# lcd_reverse_engineering_rig.net
KiCad netlist of a schematic drawn in Altium Designer
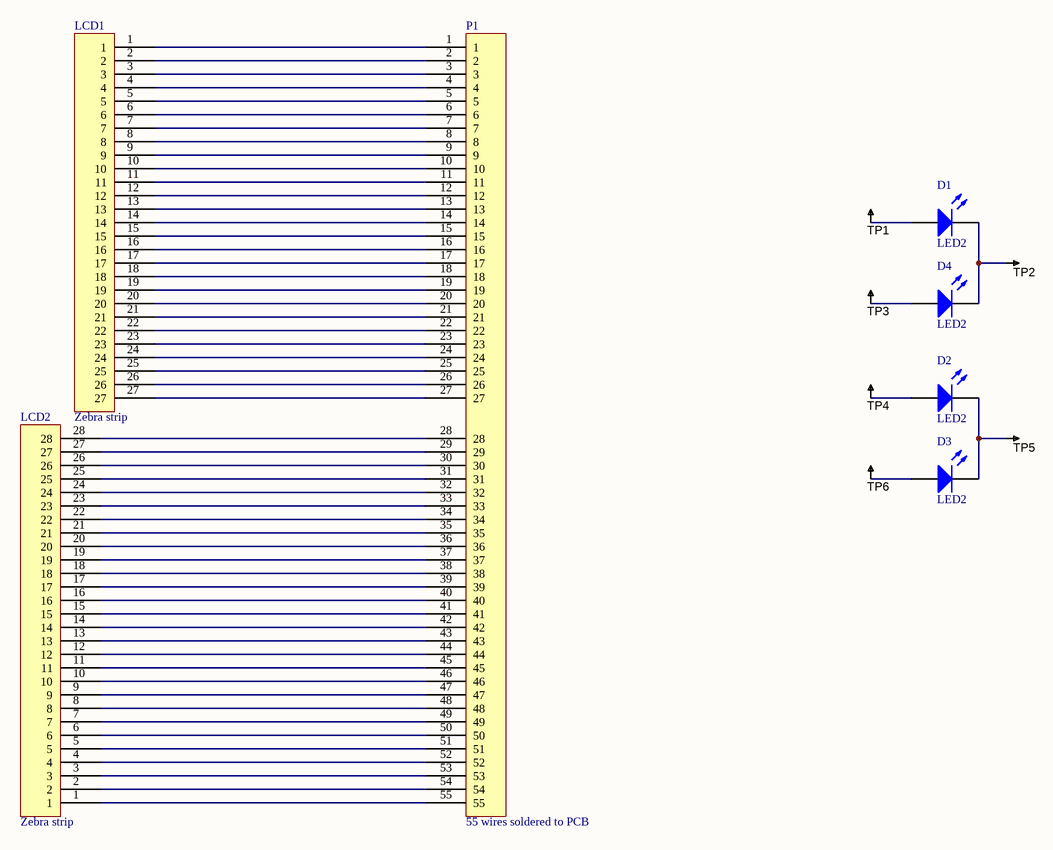
[diagram p0: lcd_reverse_engineering_rig.SchDoc]

(export (version "E")
  (design (tool "Eeschema 10.0.6"))
  (components
    (comp (ref "D1")
      (value "LED2")
      (footprint "LED_0802_90deg")
      (description "Typical RED, GREEN, YELLOW, AMBER GaAs LED")
      (fields (field (name "PUBLISHER") "Altium Limited"))
      (libsource (lib "Miscellaneous Devices") (part "LED2"))
    )
    (comp (ref "D2")
      (value "LED2")
      (footprint "LED_0802_90deg")
      (description "Typical RED, GREEN, YELLOW, AMBER GaAs LED")
      (fields (field (name "PUBLISHER") "Altium Limited"))
      (libsource (lib "Miscellaneous Devices") (part "LED2"))
    )
    (comp (ref "D3")
      (value "LED2")
      (footprint "LED_0802_90deg")
      (description "Typical RED, GREEN, YELLOW, AMBER GaAs LED")
      (fields (field (name "PUBLISHER") "Altium Limited"))
      (libsource (lib "Miscellaneous Devices") (part "LED2"))
    )
    (comp (ref "D4")
      (value "LED2")
      (footprint "LED_0802_90deg")
      (description "Typical RED, GREEN, YELLOW, AMBER GaAs LED")
      (fields (field (name "PUBLISHER") "Altium Limited"))
      (libsource (lib "Miscellaneous Devices") (part "LED2"))
    )
    (comp (ref "LCD1")
      (value "Zebra strip")
      (footprint "LCD_Connector_27")
      (description "Zebra strip connector to LCD module (27 pins)")
      (libsource (lib "watch") (part "Zebra strip 27 pin"))
    )
    (comp (ref "LCD2")
      (value "Zebra strip")
      (footprint "LCD_Connector_28")
      (description "Zebra strip connector to LCD module (28 pins)")
      (libsource (lib "watch") (part "Zebra strip 28 pin"))
    )
    (comp (ref "P1")
      (value "55 wires soldered to PCB")
      (footprint "Wires55")
      (libsource (lib "watch") (part "Wires55"))
    )
    (comp (ref "TP1")
      (value "TESTPOINT_THT_MINI")
      (footprint "THP_D38_T75_B75")
      (description "Test Point PCB mount Miniature White")
      (fields (field (name "PBL PART NUMBER") "3100-567"))
      (libsource (lib "PBL - Test Points") (part "TESTPOINT_THT_MINI"))
    )
    (comp (ref "TP2")
      (value "TESTPOINT_THT_MINI")
      (footprint "THP_D38_T75_B75")
      (description "Test Point PCB mount Miniature White")
      (fields (field (name "PBL PART NUMBER") "3100-567"))
      (libsource (lib "PBL - Test Points") (part "TESTPOINT_THT_MINI"))
    )
    (comp (ref "TP3")
      (value "TESTPOINT_THT_MINI")
      (footprint "THP_D38_T75_B75")
      (description "Test Point PCB mount Miniature White")
      (fields (field (name "PBL PART NUMBER") "3100-567"))
      (libsource (lib "PBL - Test Points") (part "TESTPOINT_THT_MINI"))
    )
    (comp (ref "TP4")
      (value "TESTPOINT_THT_MINI")
      (footprint "THP_D38_T75_B75")
      (description "Test Point PCB mount Miniature White")
      (fields (field (name "PBL PART NUMBER") "3100-567"))
      (libsource (lib "PBL - Test Points") (part "TESTPOINT_THT_MINI"))
    )
    (comp (ref "TP5")
      (value "TESTPOINT_THT_MINI")
      (footprint "THP_D38_T75_B75")
      (description "Test Point PCB mount Miniature White")
      (fields (field (name "PBL PART NUMBER") "3100-567"))
      (libsource (lib "PBL - Test Points") (part "TESTPOINT_THT_MINI"))
    )
    (comp (ref "TP6")
      (value "TESTPOINT_THT_MINI")
      (footprint "THP_D38_T75_B75")
      (description "Test Point PCB mount Miniature White")
      (fields (field (name "PBL PART NUMBER") "3100-567"))
      (libsource (lib "PBL - Test Points") (part "TESTPOINT_THT_MINI"))
    )
  )
  (nets
    (net (code "1") (name "Net-(D1-A)") (class "Default")
      (node (ref "D1") (pin "1") (pinfunction "A_1") (pintype "passive"))
      (node (ref "TP1") (pin "1") (pintype "passive"))
    )
    (net (code "2") (name "Net-(D1-K)") (class "Default")
      (node (ref "D1") (pin "2") (pinfunction "K_2") (pintype "passive"))
      (node (ref "D4") (pin "2") (pinfunction "K_2") (pintype "passive"))
      (node (ref "TP2") (pin "1") (pintype "passive"))
    )
    (net (code "3") (name "Net-(D2-A)") (class "Default")
      (node (ref "D2") (pin "1") (pinfunction "A_1") (pintype "passive"))
      (node (ref "TP4") (pin "1") (pintype "passive"))
    )
    (net (code "4") (name "Net-(D2-K)") (class "Default")
      (node (ref "D2") (pin "2") (pinfunction "K_2") (pintype "passive"))
      (node (ref "D3") (pin "2") (pinfunction "K_2") (pintype "passive"))
      (node (ref "TP5") (pin "1") (pintype "passive"))
    )
    (net (code "5") (name "Net-(D3-A)") (class "Default")
      (node (ref "D3") (pin "1") (pinfunction "A_1") (pintype "passive"))
      (node (ref "TP6") (pin "1") (pintype "passive"))
    )
    (net (code "6") (name "Net-(D4-A)") (class "Default")
      (node (ref "D4") (pin "1") (pinfunction "A_1") (pintype "passive"))
      (node (ref "TP3") (pin "1") (pintype "passive"))
    )
    (net (code "7") (name "Net-(LCD1-Pad1)") (class "Default")
      (node (ref "LCD1") (pin "1") (pinfunction "1_1") (pintype "passive"))
      (node (ref "P1") (pin "1") (pinfunction "1_1") (pintype "passive"))
    )
    (net (code "8") (name "Net-(LCD1-Pad2)") (class "Default")
      (node (ref "LCD1") (pin "2") (pinfunction "2_2") (pintype "passive"))
      (node (ref "P1") (pin "2") (pinfunction "2_2") (pintype "passive"))
    )
    (net (code "9") (name "Net-(LCD1-Pad3)") (class "Default")
      (node (ref "LCD1") (pin "3") (pinfunction "3_3") (pintype "passive"))
      (node (ref "P1") (pin "3") (pinfunction "3_3") (pintype "passive"))
    )
    (net (code "10") (name "Net-(LCD1-Pad4)") (class "Default")
      (node (ref "LCD1") (pin "4") (pinfunction "4_4") (pintype "passive"))
      (node (ref "P1") (pin "4") (pinfunction "4_4") (pintype "passive"))
    )
    (net (code "11") (name "Net-(LCD1-Pad5)") (class "Default")
      (node (ref "LCD1") (pin "5") (pinfunction "5_5") (pintype "passive"))
      (node (ref "P1") (pin "5") (pinfunction "5_5") (pintype "passive"))
    )
    (net (code "12") (name "Net-(LCD1-Pad6)") (class "Default")
      (node (ref "LCD1") (pin "6") (pinfunction "6_6") (pintype "passive"))
      (node (ref "P1") (pin "6") (pinfunction "6_6") (pintype "passive"))
    )
    (net (code "13") (name "Net-(LCD1-Pad7)") (class "Default")
      (node (ref "LCD1") (pin "7") (pinfunction "7_7") (pintype "passive"))
      (node (ref "P1") (pin "7") (pinfunction "7_7") (pintype "passive"))
    )
    (net (code "14") (name "Net-(LCD1-Pad8)") (class "Default")
      (node (ref "LCD1") (pin "8") (pinfunction "8_8") (pintype "passive"))
      (node (ref "P1") (pin "8") (pinfunction "8_8") (pintype "passive"))
    )
    (net (code "15") (name "Net-(LCD1-Pad9)") (class "Default")
      (node (ref "LCD1") (pin "9") (pinfunction "9_9") (pintype "passive"))
      (node (ref "P1") (pin "9") (pinfunction "9_9") (pintype "passive"))
    )
    (net (code "16") (name "Net-(LCD1-Pad10)") (class "Default")
      (node (ref "LCD1") (pin "10") (pinfunction "10_10") (pintype "passive"))
      (node (ref "P1") (pin "10") (pinfunction "10_10") (pintype "passive"))
    )
    (net (code "17") (name "Net-(LCD1-Pad11)") (class "Default")
      (node (ref "LCD1") (pin "11") (pinfunction "11_11") (pintype "passive"))
      (node (ref "P1") (pin "11") (pinfunction "11_11") (pintype "passive"))
    )
    (net (code "18") (name "Net-(LCD1-Pad12)") (class "Default")
      (node (ref "LCD1") (pin "12") (pinfunction "12_12") (pintype "passive"))
      (node (ref "P1") (pin "12") (pinfunction "12_12") (pintype "passive"))
    )
    (net (code "19") (name "Net-(LCD1-Pad13)") (class "Default")
      (node (ref "LCD1") (pin "13") (pinfunction "13_13") (pintype "passive"))
      (node (ref "P1") (pin "13") (pinfunction "13_13") (pintype "passive"))
    )
    (net (code "20") (name "Net-(LCD1-Pad14)") (class "Default")
      (node (ref "LCD1") (pin "14") (pinfunction "14_14") (pintype "passive"))
      (node (ref "P1") (pin "14") (pinfunction "14_14") (pintype "passive"))
    )
    (net (code "21") (name "Net-(LCD1-Pad15)") (class "Default")
      (node (ref "LCD1") (pin "15") (pinfunction "15_15") (pintype "passive"))
      (node (ref "P1") (pin "15") (pinfunction "15_15") (pintype "passive"))
    )
    (net (code "22") (name "Net-(LCD1-Pad16)") (class "Default")
      (node (ref "LCD1") (pin "16") (pinfunction "16_16") (pintype "passive"))
      (node (ref "P1") (pin "16") (pinfunction "16_16") (pintype "passive"))
    )
    (net (code "23") (name "Net-(LCD1-Pad17)") (class "Default")
      (node (ref "LCD1") (pin "17") (pinfunction "17_17") (pintype "passive"))
      (node (ref "P1") (pin "17") (pinfunction "17_17") (pintype "passive"))
    )
    (net (code "24") (name "Net-(LCD1-Pad18)") (class "Default")
      (node (ref "LCD1") (pin "18") (pinfunction "18_18") (pintype "passive"))
      (node (ref "P1") (pin "18") (pinfunction "18_18") (pintype "passive"))
    )
    (net (code "25") (name "Net-(LCD1-Pad19)") (class "Default")
      (node (ref "LCD1") (pin "19") (pinfunction "19_19") (pintype "passive"))
      (node (ref "P1") (pin "19") (pinfunction "19_19") (pintype "passive"))
    )
    (net (code "26") (name "Net-(LCD1-Pad20)") (class "Default")
      (node (ref "LCD1") (pin "20") (pinfunction "20_20") (pintype "passive"))
      (node (ref "P1") (pin "20") (pinfunction "20_20") (pintype "passive"))
    )
    (net (code "27") (name "Net-(LCD1-Pad21)") (class "Default")
      (node (ref "LCD1") (pin "21") (pinfunction "21_21") (pintype "passive"))
      (node (ref "P1") (pin "21") (pinfunction "21_21") (pintype "passive"))
    )
    (net (code "28") (name "Net-(LCD1-Pad22)") (class "Default")
      (node (ref "LCD1") (pin "22") (pinfunction "22_22") (pintype "passive"))
      (node (ref "P1") (pin "22") (pinfunction "22_22") (pintype "passive"))
    )
    (net (code "29") (name "Net-(LCD1-Pad23)") (class "Default")
      (node (ref "LCD1") (pin "23") (pinfunction "23_23") (pintype "passive"))
      (node (ref "P1") (pin "23") (pinfunction "23_23") (pintype "passive"))
    )
    (net (code "30") (name "Net-(LCD1-Pad24)") (class "Default")
      (node (ref "LCD1") (pin "24") (pinfunction "24_24") (pintype "passive"))
      (node (ref "P1") (pin "24") (pinfunction "24_24") (pintype "passive"))
    )
    (net (code "31") (name "Net-(LCD1-Pad25)") (class "Default")
      (node (ref "LCD1") (pin "25") (pinfunction "25_25") (pintype "passive"))
      (node (ref "P1") (pin "25") (pinfunction "25_25") (pintype "passive"))
    )
    (net (code "32") (name "Net-(LCD1-Pad26)") (class "Default")
      (node (ref "LCD1") (pin "26") (pinfunction "26_26") (pintype "passive"))
      (node (ref "P1") (pin "26") (pinfunction "26_26") (pintype "passive"))
    )
    (net (code "33") (name "Net-(LCD1-Pad27)") (class "Default")
      (node (ref "LCD1") (pin "27") (pinfunction "27_27") (pintype "passive"))
      (node (ref "P1") (pin "27") (pinfunction "27_27") (pintype "passive"))
    )
    (net (code "34") (name "Net-(LCD2-Pad1)") (class "Default")
      (node (ref "LCD2") (pin "1") (pinfunction "1_1") (pintype "passive"))
      (node (ref "P1") (pin "55") (pinfunction "55_55") (pintype "passive"))
    )
    (net (code "35") (name "Net-(LCD2-Pad2)") (class "Default")
      (node (ref "LCD2") (pin "2") (pinfunction "2_2") (pintype "passive"))
      (node (ref "P1") (pin "54") (pinfunction "54_54") (pintype "passive"))
    )
    (net (code "36") (name "Net-(LCD2-Pad3)") (class "Default")
      (node (ref "LCD2") (pin "3") (pinfunction "3_3") (pintype "passive"))
      (node (ref "P1") (pin "53") (pinfunction "53_53") (pintype "passive"))
    )
    (net (code "37") (name "Net-(LCD2-Pad4)") (class "Default")
      (node (ref "LCD2") (pin "4") (pinfunction "4_4") (pintype "passive"))
      (node (ref "P1") (pin "52") (pinfunction "52_52") (pintype "passive"))
    )
    (net (code "38") (name "Net-(LCD2-Pad5)") (class "Default")
      (node (ref "LCD2") (pin "5") (pinfunction "5_5") (pintype "passive"))
      (node (ref "P1") (pin "51") (pinfunction "51_51") (pintype "passive"))
    )
    (net (code "39") (name "Net-(LCD2-Pad6)") (class "Default")
      (node (ref "LCD2") (pin "6") (pinfunction "6_6") (pintype "passive"))
      (node (ref "P1") (pin "50") (pinfunction "50_50") (pintype "passive"))
    )
    (net (code "40") (name "Net-(LCD2-Pad7)") (class "Default")
      (node (ref "LCD2") (pin "7") (pinfunction "7_7") (pintype "passive"))
      (node (ref "P1") (pin "49") (pinfunction "49_49") (pintype "passive"))
    )
    (net (code "41") (name "Net-(LCD2-Pad8)") (class "Default")
      (node (ref "LCD2") (pin "8") (pinfunction "8_8") (pintype "passive"))
      (node (ref "P1") (pin "48") (pinfunction "48_48") (pintype "passive"))
    )
    (net (code "42") (name "Net-(LCD2-Pad9)") (class "Default")
      (node (ref "LCD2") (pin "9") (pinfunction "9_9") (pintype "passive"))
      (node (ref "P1") (pin "47") (pinfunction "47_47") (pintype "passive"))
    )
    (net (code "43") (name "Net-(LCD2-Pad10)") (class "Default")
      (node (ref "LCD2") (pin "10") (pinfunction "10_10") (pintype "passive"))
      (node (ref "P1") (pin "46") (pinfunction "46_46") (pintype "passive"))
    )
    (net (code "44") (name "Net-(LCD2-Pad11)") (class "Default")
      (node (ref "LCD2") (pin "11") (pinfunction "11_11") (pintype "passive"))
      (node (ref "P1") (pin "45") (pinfunction "45_45") (pintype "passive"))
    )
    (net (code "45") (name "Net-(LCD2-Pad12)") (class "Default")
      (node (ref "LCD2") (pin "12") (pinfunction "12_12") (pintype "passive"))
      (node (ref "P1") (pin "44") (pinfunction "44_44") (pintype "passive"))
    )
    (net (code "46") (name "Net-(LCD2-Pad13)") (class "Default")
      (node (ref "LCD2") (pin "13") (pinfunction "13_13") (pintype "passive"))
      (node (ref "P1") (pin "43") (pinfunction "43_43") (pintype "passive"))
    )
    (net (code "47") (name "Net-(LCD2-Pad14)") (class "Default")
      (node (ref "LCD2") (pin "14") (pinfunction "14_14") (pintype "passive"))
      (node (ref "P1") (pin "42") (pinfunction "42_42") (pintype "passive"))
    )
    (net (code "48") (name "Net-(LCD2-Pad15)") (class "Default")
      (node (ref "LCD2") (pin "15") (pinfunction "15_15") (pintype "passive"))
      (node (ref "P1") (pin "41") (pinfunction "41_41") (pintype "passive"))
    )
    (net (code "49") (name "Net-(LCD2-Pad16)") (class "Default")
      (node (ref "LCD2") (pin "16") (pinfunction "16_16") (pintype "passive"))
      (node (ref "P1") (pin "40") (pinfunction "40_40") (pintype "passive"))
    )
    (net (code "50") (name "Net-(LCD2-Pad17)") (class "Default")
      (node (ref "LCD2") (pin "17") (pinfunction "17_17") (pintype "passive"))
      (node (ref "P1") (pin "39") (pinfunction "39_39") (pintype "passive"))
    )
    (net (code "51") (name "Net-(LCD2-Pad18)") (class "Default")
      (node (ref "LCD2") (pin "18") (pinfunction "18_18") (pintype "passive"))
      (node (ref "P1") (pin "38") (pinfunction "38_38") (pintype "passive"))
    )
    (net (code "52") (name "Net-(LCD2-Pad19)") (class "Default")
      (node (ref "LCD2") (pin "19") (pinfunction "19_19") (pintype "passive"))
      (node (ref "P1") (pin "37") (pinfunction "37_37") (pintype "passive"))
    )
    (net (code "53") (name "Net-(LCD2-Pad20)") (class "Default")
      (node (ref "LCD2") (pin "20") (pinfunction "20_20") (pintype "passive"))
      (node (ref "P1") (pin "36") (pinfunction "36_36") (pintype "passive"))
    )
    (net (code "54") (name "Net-(LCD2-Pad21)") (class "Default")
      (node (ref "LCD2") (pin "21") (pinfunction "21_21") (pintype "passive"))
      (node (ref "P1") (pin "35") (pinfunction "35_35") (pintype "passive"))
    )
    (net (code "55") (name "Net-(LCD2-Pad22)") (class "Default")
      (node (ref "LCD2") (pin "22") (pinfunction "22_22") (pintype "passive"))
      (node (ref "P1") (pin "34") (pinfunction "34_34") (pintype "passive"))
    )
    (net (code "56") (name "Net-(LCD2-Pad23)") (class "Default")
      (node (ref "LCD2") (pin "23") (pinfunction "23_23") (pintype "passive"))
      (node (ref "P1") (pin "33") (pinfunction "33_33") (pintype "passive"))
    )
    (net (code "57") (name "Net-(LCD2-Pad24)") (class "Default")
      (node (ref "LCD2") (pin "24") (pinfunction "24_24") (pintype "passive"))
      (node (ref "P1") (pin "32") (pinfunction "32_32") (pintype "passive"))
    )
    (net (code "58") (name "Net-(LCD2-Pad25)") (class "Default")
      (node (ref "LCD2") (pin "25") (pinfunction "25_25") (pintype "passive"))
      (node (ref "P1") (pin "31") (pinfunction "31_31") (pintype "passive"))
    )
    (net (code "59") (name "Net-(LCD2-Pad26)") (class "Default")
      (node (ref "LCD2") (pin "26") (pinfunction "26_26") (pintype "passive"))
      (node (ref "P1") (pin "30") (pinfunction "30_30") (pintype "passive"))
    )
    (net (code "60") (name "Net-(LCD2-Pad27)") (class "Default")
      (node (ref "LCD2") (pin "27") (pinfunction "27_27") (pintype "passive"))
      (node (ref "P1") (pin "29") (pinfunction "29_29") (pintype "passive"))
    )
    (net (code "61") (name "Net-(LCD2-Pad28)") (class "Default")
      (node (ref "LCD2") (pin "28") (pinfunction "28_28") (pintype "passive"))
      (node (ref "P1") (pin "28") (pinfunction "28_28") (pintype "passive"))
    )
  )
)
